# TriggerBoard_v4.net
KiCad netlist of a schematic drawn in EAGLE
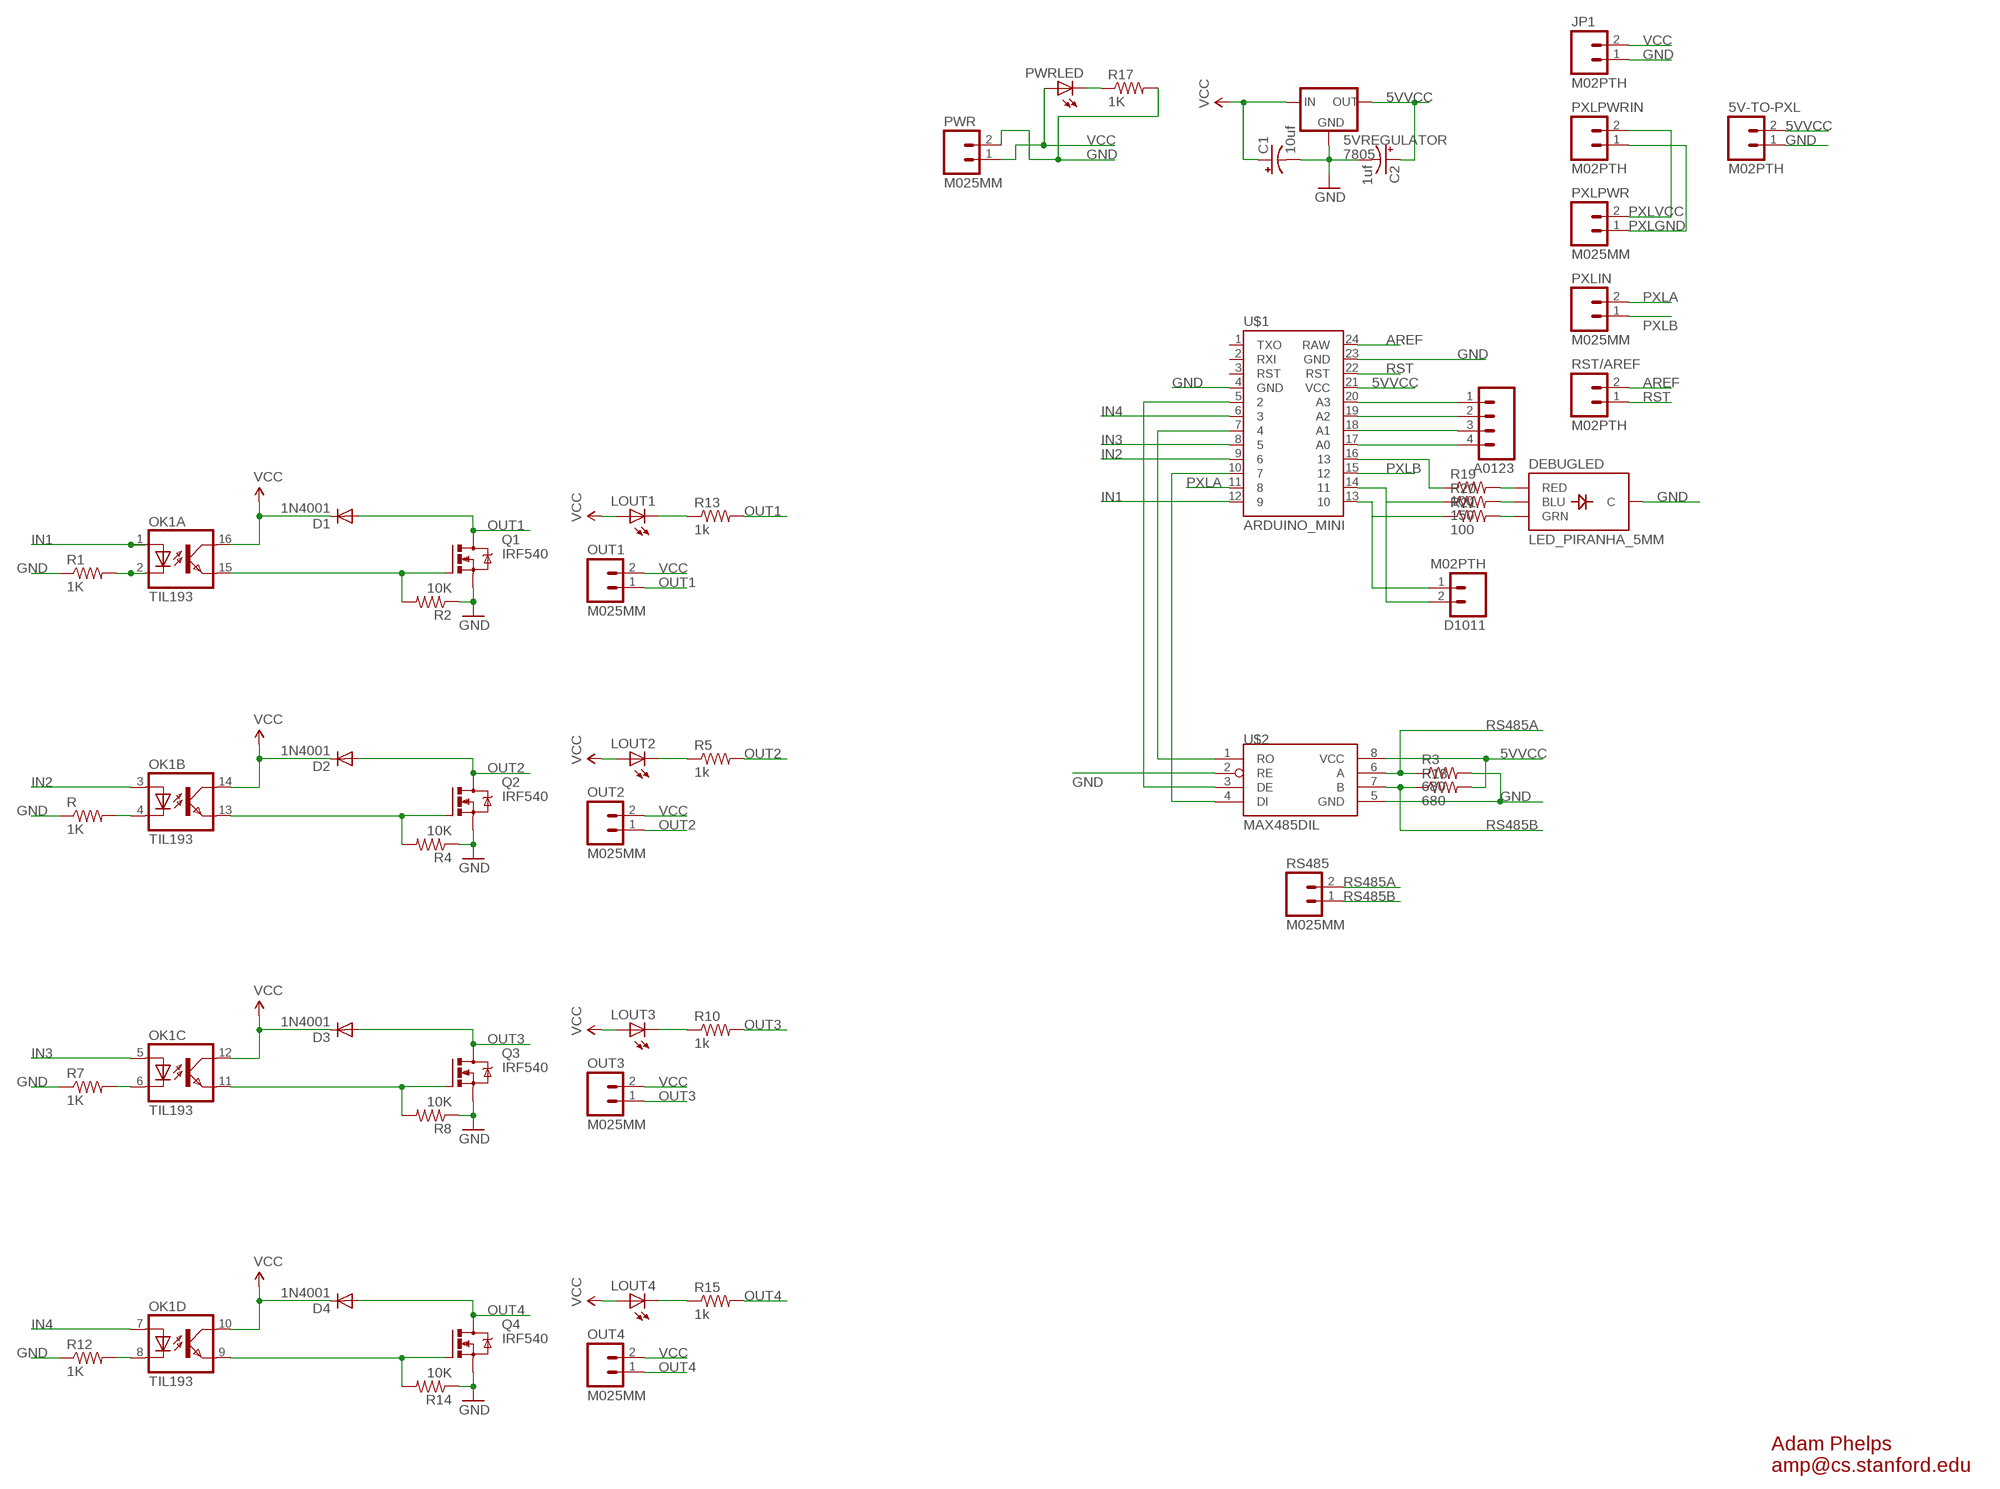
[diagram p0: schematic, sheet 1]

(export (version "E")
  (design (tool "Eeschema 10.0.6"))
  (components
    (comp (ref "5V-TO-PXL")
      (value "M02PTH")
      (footprint "eagle-import:1X02")
      (libsource (lib "eagle-import") (part "M02PTH"))
    )
    (comp (ref "5VREGULATOR")
      (value "7805")
      (footprint "eagle-import:TO220-IGO")
      (libsource (lib "eagle-import") (part "V_REG_78XXSINK"))
    )
    (comp (ref "A0123")
      (value "M04PTH")
      (footprint "eagle-import:1X04")
      (libsource (lib "eagle-import") (part "M04PTH"))
    )
    (comp (ref "C1")
      (value "10uf")
      (footprint "eagle-import:CPOL-RADIAL-10UF-25V")
      (libsource (lib "eagle-import") (part "CAP_POLPTH2"))
    )
    (comp (ref "C2")
      (value "1uf")
      (footprint "eagle-import:CPOL-RADIAL-10UF-25V")
      (libsource (lib "eagle-import") (part "CAP_POLPTH2"))
    )
    (comp (ref "D1")
      (value "1N4001")
      (footprint "eagle-import:DIODE-1N4001")
      (libsource (lib "eagle-import") (part "DIODEPTH"))
    )
    (comp (ref "D2")
      (value "1N4001")
      (footprint "eagle-import:DIODE-1N4001")
      (libsource (lib "eagle-import") (part "DIODEPTH"))
    )
    (comp (ref "D3")
      (value "1N4001")
      (footprint "eagle-import:DIODE-1N4001")
      (libsource (lib "eagle-import") (part "DIODEPTH"))
    )
    (comp (ref "D4")
      (value "1N4001")
      (footprint "eagle-import:DIODE-1N4001")
      (libsource (lib "eagle-import") (part "DIODEPTH"))
    )
    (comp (ref "D1011")
      (value "M02PTH")
      (footprint "eagle-import:1X02")
      (libsource (lib "eagle-import") (part "M02PTH"))
    )
    (comp (ref "DEBUGLED")
      (value "LED_PIRANHA_5MM")
      (footprint "eagle-import:LED_PIRANHA_5MM")
      (libsource (lib "eagle-import") (part "LED_PIRANHA_5MM"))
    )
    (comp (ref "JP1")
      (value "M02PTH")
      (footprint "eagle-import:1X02")
      (libsource (lib "eagle-import") (part "M02PTH"))
    )
    (comp (ref "LOUT1")
      (value "LED3MM")
      (footprint "eagle-import:LED3MM")
      (libsource (lib "eagle-import") (part "LED3MM"))
    )
    (comp (ref "LOUT2")
      (value "LED3MM")
      (footprint "eagle-import:LED3MM")
      (libsource (lib "eagle-import") (part "LED3MM"))
    )
    (comp (ref "LOUT3")
      (value "LED3MM")
      (footprint "eagle-import:LED3MM")
      (libsource (lib "eagle-import") (part "LED3MM"))
    )
    (comp (ref "LOUT4")
      (value "LED3MM")
      (footprint "eagle-import:LED3MM")
      (libsource (lib "eagle-import") (part "LED3MM"))
    )
    (comp (ref "OK1")
      (value "TIL193")
      (footprint "eagle-import:DIL16")
      (libsource (lib "eagle-import") (part "TIL193"))
    )
    (comp (ref "OUT1")
      (value "M025MM")
      (footprint "eagle-import:SCREWTERMINAL-5MM-2")
      (libsource (lib "eagle-import") (part "M025MM"))
    )
    (comp (ref "OUT2")
      (value "M025MM")
      (footprint "eagle-import:SCREWTERMINAL-5MM-2")
      (libsource (lib "eagle-import") (part "M025MM"))
    )
    (comp (ref "OUT3")
      (value "M025MM")
      (footprint "eagle-import:SCREWTERMINAL-5MM-2")
      (libsource (lib "eagle-import") (part "M025MM"))
    )
    (comp (ref "OUT4")
      (value "M025MM")
      (footprint "eagle-import:SCREWTERMINAL-5MM-2")
      (libsource (lib "eagle-import") (part "M025MM"))
    )
    (comp (ref "PWR")
      (value "M025MM")
      (footprint "eagle-import:SCREWTERMINAL-5MM-2")
      (libsource (lib "eagle-import") (part "M025MM"))
    )
    (comp (ref "PWRLED")
      (value "LED5MM")
      (footprint "eagle-import:LED5MM")
      (libsource (lib "eagle-import") (part "LED5MM"))
    )
    (comp (ref "PXLIN")
      (value "M025MM")
      (footprint "eagle-import:SCREWTERMINAL-5MM-2")
      (libsource (lib "eagle-import") (part "M025MM"))
    )
    (comp (ref "PXLPWR")
      (value "M025MM")
      (footprint "eagle-import:SCREWTERMINAL-5MM-2")
      (libsource (lib "eagle-import") (part "M025MM"))
    )
    (comp (ref "PXLPWRIN")
      (value "M02PTH")
      (footprint "eagle-import:1X02")
      (libsource (lib "eagle-import") (part "M02PTH"))
    )
    (comp (ref "Q1")
      (value "IRF540")
      (footprint "eagle-import:TO220BV")
      (libsource (lib "eagle-import") (part "IRF540"))
    )
    (comp (ref "Q2")
      (value "IRF540")
      (footprint "eagle-import:TO220BV")
      (libsource (lib "eagle-import") (part "IRF540"))
    )
    (comp (ref "Q3")
      (value "IRF540")
      (footprint "eagle-import:TO220BV")
      (libsource (lib "eagle-import") (part "IRF540"))
    )
    (comp (ref "Q4")
      (value "IRF540")
      (footprint "eagle-import:TO220BV")
      (libsource (lib "eagle-import") (part "IRF540"))
    )
    (comp (ref "R")
      (value "1K")
      (footprint "eagle-import:AXIAL-0.4")
      (libsource (lib "eagle-import") (part "RESISTORPTH-1/4W"))
    )
    (comp (ref "R1")
      (value "1K")
      (footprint "eagle-import:AXIAL-0.4")
      (libsource (lib "eagle-import") (part "RESISTORPTH-1/4W"))
    )
    (comp (ref "R2")
      (value "10K")
      (footprint "eagle-import:AXIAL-0.4")
      (libsource (lib "eagle-import") (part "RESISTORPTH-1/4W"))
    )
    (comp (ref "R3")
      (value "680")
      (footprint "eagle-import:AXIAL-0.4")
      (libsource (lib "eagle-import") (part "RESISTORPTH-1/4W"))
    )
    (comp (ref "R4")
      (value "10K")
      (footprint "eagle-import:AXIAL-0.4")
      (libsource (lib "eagle-import") (part "RESISTORPTH-1/4W"))
    )
    (comp (ref "R5")
      (value "1k")
      (footprint "eagle-import:AXIAL-0.4")
      (libsource (lib "eagle-import") (part "RESISTORPTH-1/4W"))
    )
    (comp (ref "R7")
      (value "1K")
      (footprint "eagle-import:AXIAL-0.4")
      (libsource (lib "eagle-import") (part "RESISTORPTH-1/4W"))
    )
    (comp (ref "R8")
      (value "10K")
      (footprint "eagle-import:AXIAL-0.4")
      (libsource (lib "eagle-import") (part "RESISTORPTH-1/4W"))
    )
    (comp (ref "R10")
      (value "1k")
      (footprint "eagle-import:AXIAL-0.4")
      (libsource (lib "eagle-import") (part "RESISTORPTH-1/4W"))
    )
    (comp (ref "R12")
      (value "1K")
      (footprint "eagle-import:AXIAL-0.4")
      (libsource (lib "eagle-import") (part "RESISTORPTH-1/4W"))
    )
    (comp (ref "R13")
      (value "1k")
      (footprint "eagle-import:AXIAL-0.4")
      (libsource (lib "eagle-import") (part "RESISTORPTH-1/4W"))
    )
    (comp (ref "R14")
      (value "10K")
      (footprint "eagle-import:AXIAL-0.4")
      (libsource (lib "eagle-import") (part "RESISTORPTH-1/4W"))
    )
    (comp (ref "R15")
      (value "1k")
      (footprint "eagle-import:AXIAL-0.4")
      (libsource (lib "eagle-import") (part "RESISTORPTH-1/4W"))
    )
    (comp (ref "R17")
      (value "1K")
      (footprint "eagle-import:AXIAL-0.4")
      (libsource (lib "eagle-import") (part "RESISTORPTH-1/4W"))
    )
    (comp (ref "R18")
      (value "680")
      (footprint "eagle-import:AXIAL-0.4")
      (libsource (lib "eagle-import") (part "RESISTORPTH-1/4W"))
    )
    (comp (ref "R19")
      (value "100")
      (footprint "eagle-import:AXIAL-0.4")
      (libsource (lib "eagle-import") (part "RESISTORPTH-1/4W"))
    )
    (comp (ref "R20")
      (value "150")
      (footprint "eagle-import:AXIAL-0.4")
      (libsource (lib "eagle-import") (part "RESISTORPTH-1/4W"))
    )
    (comp (ref "R21")
      (value "100")
      (footprint "eagle-import:AXIAL-0.4")
      (libsource (lib "eagle-import") (part "RESISTORPTH-1/4W"))
    )
    (comp (ref "RS485")
      (value "M025MM")
      (footprint "eagle-import:SCREWTERMINAL-5MM-2")
      (libsource (lib "eagle-import") (part "M025MM"))
    )
    (comp (ref "RST/AREF")
      (value "M02PTH")
      (footprint "eagle-import:1X02")
      (libsource (lib "eagle-import") (part "M02PTH"))
    )
    (comp (ref "U$1")
      (value "ARDUINO_MINI")
      (footprint "eagle-import:ARDUINO_MINI")
      (libsource (lib "eagle-import") (part "ARDUINO_MINI"))
    )
    (comp (ref "U$2")
      (value "MAX485DIL")
      (footprint "eagle-import:DIL08")
      (libsource (lib "eagle-import") (part "MAX485DIL"))
    )
  )
  (nets
    (net (code "1") (name "/5VVCC") (class "Default")
      (node (ref "5V-TO-PXL") (pin "2") (pinfunction "2_2") (pintype "passive"))
      (node (ref "5VREGULATOR") (pin "OUT") (pinfunction "OUT_OUT") (pintype "output"))
      (node (ref "C2") (pin "1") (pinfunction "+_1") (pintype "passive"))
      (node (ref "R18") (pin "P$2") (pinfunction "2_P$2") (pintype "passive"))
      (node (ref "U$1") (pin "21") (pinfunction "VCC_21") (pintype "bidirectional"))
      (node (ref "U$2") (pin "8") (pinfunction "VCC_8") (pintype "bidirectional"))
    )
    (net (code "2") (name "/AREF") (class "Default")
      (node (ref "RST/AREF") (pin "2") (pinfunction "2_2") (pintype "passive"))
      (node (ref "U$1") (pin "24") (pinfunction "RAW_24") (pintype "bidirectional"))
    )
    (net (code "3") (name "/IN1") (class "Default")
      (node (ref "OK1") (pin "1") (pinfunction "A_1") (pintype "passive"))
      (node (ref "U$1") (pin "12") (pinfunction "9_12") (pintype "bidirectional"))
    )
    (net (code "4") (name "/IN2") (class "Default")
      (node (ref "OK1") (pin "3") (pinfunction "A_3") (pintype "passive"))
      (node (ref "U$1") (pin "9") (pinfunction "6_9") (pintype "bidirectional"))
    )
    (net (code "5") (name "/IN3") (class "Default")
      (node (ref "OK1") (pin "5") (pinfunction "A_5") (pintype "passive"))
      (node (ref "U$1") (pin "8") (pinfunction "5_8") (pintype "bidirectional"))
    )
    (net (code "6") (name "/IN4") (class "Default")
      (node (ref "OK1") (pin "7") (pinfunction "A_7") (pintype "passive"))
      (node (ref "U$1") (pin "6") (pinfunction "3_6") (pintype "bidirectional"))
    )
    (net (code "7") (name "/OUT1") (class "Default")
      (node (ref "D1") (pin "A") (pinfunction "A_A") (pintype "passive"))
      (node (ref "OUT1") (pin "1") (pinfunction "1_1") (pintype "passive"))
      (node (ref "Q1") (pin "D") (pinfunction "D_D") (pintype "passive"))
      (node (ref "R13") (pin "P$2") (pinfunction "2_P$2") (pintype "passive"))
    )
    (net (code "8") (name "/OUT2") (class "Default")
      (node (ref "D2") (pin "A") (pinfunction "A_A") (pintype "passive"))
      (node (ref "OUT2") (pin "1") (pinfunction "1_1") (pintype "passive"))
      (node (ref "Q2") (pin "D") (pinfunction "D_D") (pintype "passive"))
      (node (ref "R5") (pin "P$2") (pinfunction "2_P$2") (pintype "passive"))
    )
    (net (code "9") (name "/OUT3") (class "Default")
      (node (ref "D3") (pin "A") (pinfunction "A_A") (pintype "passive"))
      (node (ref "OUT3") (pin "1") (pinfunction "1_1") (pintype "passive"))
      (node (ref "Q3") (pin "D") (pinfunction "D_D") (pintype "passive"))
      (node (ref "R10") (pin "P$2") (pinfunction "2_P$2") (pintype "passive"))
    )
    (net (code "10") (name "/OUT4") (class "Default")
      (node (ref "D4") (pin "A") (pinfunction "A_A") (pintype "passive"))
      (node (ref "OUT4") (pin "1") (pinfunction "1_1") (pintype "passive"))
      (node (ref "Q4") (pin "D") (pinfunction "D_D") (pintype "passive"))
      (node (ref "R15") (pin "P$2") (pinfunction "2_P$2") (pintype "passive"))
    )
    (net (code "11") (name "/PXLA") (class "Default")
      (node (ref "PXLIN") (pin "2") (pinfunction "2_2") (pintype "passive"))
      (node (ref "U$1") (pin "11") (pinfunction "8_11") (pintype "bidirectional"))
    )
    (net (code "12") (name "/PXLB") (class "Default")
      (node (ref "PXLIN") (pin "1") (pinfunction "1_1") (pintype "passive"))
      (node (ref "U$1") (pin "15") (pinfunction "12_15") (pintype "bidirectional"))
    )
    (net (code "13") (name "/PXLGND") (class "Default")
      (node (ref "PXLPWR") (pin "1") (pinfunction "1_1") (pintype "passive"))
      (node (ref "PXLPWRIN") (pin "1") (pinfunction "1_1") (pintype "passive"))
    )
    (net (code "14") (name "/PXLVCC") (class "Default")
      (node (ref "PXLPWR") (pin "2") (pinfunction "2_2") (pintype "passive"))
      (node (ref "PXLPWRIN") (pin "2") (pinfunction "2_2") (pintype "passive"))
    )
    (net (code "15") (name "/RS485A") (class "Default")
      (node (ref "R3") (pin "P$1") (pinfunction "1_P$1") (pintype "passive"))
      (node (ref "RS485") (pin "2") (pinfunction "2_2") (pintype "passive"))
      (node (ref "U$2") (pin "6") (pinfunction "A_6") (pintype "bidirectional"))
    )
    (net (code "16") (name "/RS485B") (class "Default")
      (node (ref "R18") (pin "P$1") (pinfunction "1_P$1") (pintype "passive"))
      (node (ref "RS485") (pin "1") (pinfunction "1_1") (pintype "passive"))
      (node (ref "U$2") (pin "7") (pinfunction "B_7") (pintype "bidirectional"))
    )
    (net (code "17") (name "/RST") (class "Default")
      (node (ref "RST/AREF") (pin "1") (pinfunction "1_1") (pintype "passive"))
      (node (ref "U$1") (pin "22") (pinfunction "RST_22") (pintype "bidirectional"))
    )
    (net (code "18") (name "GND") (class "Default")
      (node (ref "5V-TO-PXL") (pin "1") (pinfunction "1_1") (pintype "passive"))
      (node (ref "5VREGULATOR") (pin "GND") (pinfunction "GND_GND") (pintype "input"))
      (node (ref "C1") (pin "2") (pinfunction "-_2") (pintype "passive"))
      (node (ref "C2") (pin "2") (pinfunction "-_2") (pintype "passive"))
      (node (ref "DEBUGLED") (pin "-") (pinfunction "C_-") (pintype "bidirectional"))
      (node (ref "JP1") (pin "1") (pinfunction "1_1") (pintype "passive"))
      (node (ref "PWR") (pin "2") (pinfunction "2_2") (pintype "passive"))
      (node (ref "Q1") (pin "S") (pinfunction "S_S") (pintype "passive"))
      (node (ref "Q2") (pin "S") (pinfunction "S_S") (pintype "passive"))
      (node (ref "Q3") (pin "S") (pinfunction "S_S") (pintype "passive"))
      (node (ref "Q4") (pin "S") (pinfunction "S_S") (pintype "passive"))
      (node (ref "R") (pin "P$1") (pinfunction "1_P$1") (pintype "passive"))
      (node (ref "R1") (pin "P$1") (pinfunction "1_P$1") (pintype "passive"))
      (node (ref "R12") (pin "P$1") (pinfunction "1_P$1") (pintype "passive"))
      (node (ref "R14") (pin "P$1") (pinfunction "1_P$1") (pintype "passive"))
      (node (ref "R17") (pin "P$2") (pinfunction "2_P$2") (pintype "passive"))
      (node (ref "R2") (pin "P$1") (pinfunction "1_P$1") (pintype "passive"))
      (node (ref "R3") (pin "P$2") (pinfunction "2_P$2") (pintype "passive"))
      (node (ref "R4") (pin "P$1") (pinfunction "1_P$1") (pintype "passive"))
      (node (ref "R7") (pin "P$1") (pinfunction "1_P$1") (pintype "passive"))
      (node (ref "R8") (pin "P$1") (pinfunction "1_P$1") (pintype "passive"))
      (node (ref "U$1") (pin "23") (pinfunction "GND_23") (pintype "bidirectional"))
      (node (ref "U$1") (pin "4") (pinfunction "GND_4") (pintype "bidirectional"))
      (node (ref "U$2") (pin "2") (pinfunction "RE_2") (pintype "bidirectional"))
      (node (ref "U$2") (pin "5") (pinfunction "GND_5") (pintype "bidirectional"))
    )
    (net (code "19") (name "Net-(DEBUGLED-BLU)") (class "Default")
      (node (ref "DEBUGLED") (pin "B") (pinfunction "BLU_B") (pintype "bidirectional"))
      (node (ref "R20") (pin "P$2") (pinfunction "2_P$2") (pintype "passive"))
    )
    (net (code "20") (name "Net-(DEBUGLED-GRN)") (class "Default")
      (node (ref "DEBUGLED") (pin "G") (pinfunction "GRN_G") (pintype "bidirectional"))
      (node (ref "R21") (pin "P$2") (pinfunction "2_P$2") (pintype "passive"))
    )
    (net (code "21") (name "Net-(DEBUGLED-RED)") (class "Default")
      (node (ref "DEBUGLED") (pin "R") (pinfunction "RED_R") (pintype "bidirectional"))
      (node (ref "R19") (pin "P$2") (pinfunction "2_P$2") (pintype "passive"))
    )
    (net (code "22") (name "Net-(LOUT1-C)") (class "Default")
      (node (ref "LOUT1") (pin "K") (pinfunction "C_K") (pintype "passive"))
      (node (ref "R13") (pin "P$1") (pinfunction "1_P$1") (pintype "passive"))
    )
    (net (code "23") (name "Net-(LOUT2-C)") (class "Default")
      (node (ref "LOUT2") (pin "K") (pinfunction "C_K") (pintype "passive"))
      (node (ref "R5") (pin "P$1") (pinfunction "1_P$1") (pintype "passive"))
    )
    (net (code "24") (name "Net-(LOUT3-C)") (class "Default")
      (node (ref "LOUT3") (pin "K") (pinfunction "C_K") (pintype "passive"))
      (node (ref "R10") (pin "P$1") (pinfunction "1_P$1") (pintype "passive"))
    )
    (net (code "25") (name "Net-(LOUT4-C)") (class "Default")
      (node (ref "LOUT4") (pin "K") (pinfunction "C_K") (pintype "passive"))
      (node (ref "R15") (pin "P$1") (pinfunction "1_P$1") (pintype "passive"))
    )
    (net (code "26") (name "Net-(OK1A-C)") (class "Default")
      (node (ref "OK1") (pin "2") (pinfunction "C_2") (pintype "passive"))
      (node (ref "R1") (pin "P$2") (pinfunction "2_P$2") (pintype "passive"))
    )
    (net (code "27") (name "Net-(OK1A-EMIT)") (class "Default")
      (node (ref "OK1") (pin "15") (pinfunction "EMIT_15") (pintype "passive"))
      (node (ref "Q1") (pin "G") (pinfunction "G_G") (pintype "passive"))
      (node (ref "R2") (pin "P$2") (pinfunction "2_P$2") (pintype "passive"))
    )
    (net (code "28") (name "Net-(OK1B-C)") (class "Default")
      (node (ref "OK1") (pin "4") (pinfunction "C_4") (pintype "passive"))
      (node (ref "R") (pin "P$2") (pinfunction "2_P$2") (pintype "passive"))
    )
    (net (code "29") (name "Net-(OK1B-EMIT)") (class "Default")
      (node (ref "OK1") (pin "13") (pinfunction "EMIT_13") (pintype "passive"))
      (node (ref "Q2") (pin "G") (pinfunction "G_G") (pintype "passive"))
      (node (ref "R4") (pin "P$2") (pinfunction "2_P$2") (pintype "passive"))
    )
    (net (code "30") (name "Net-(OK1C-C)") (class "Default")
      (node (ref "OK1") (pin "6") (pinfunction "C_6") (pintype "passive"))
      (node (ref "R7") (pin "P$2") (pinfunction "2_P$2") (pintype "passive"))
    )
    (net (code "31") (name "Net-(OK1C-EMIT)") (class "Default")
      (node (ref "OK1") (pin "11") (pinfunction "EMIT_11") (pintype "passive"))
      (node (ref "Q3") (pin "G") (pinfunction "G_G") (pintype "passive"))
      (node (ref "R8") (pin "P$2") (pinfunction "2_P$2") (pintype "passive"))
    )
    (net (code "32") (name "Net-(OK1D-C)") (class "Default")
      (node (ref "OK1") (pin "8") (pinfunction "C_8") (pintype "passive"))
      (node (ref "R12") (pin "P$2") (pinfunction "2_P$2") (pintype "passive"))
    )
    (net (code "33") (name "Net-(OK1D-EMIT)") (class "Default")
      (node (ref "OK1") (pin "9") (pinfunction "EMIT_9") (pintype "passive"))
      (node (ref "Q4") (pin "G") (pinfunction "G_G") (pintype "passive"))
      (node (ref "R14") (pin "P$2") (pinfunction "2_P$2") (pintype "passive"))
    )
    (net (code "34") (name "Net-(PWRLED-C)") (class "Default")
      (node (ref "PWRLED") (pin "K") (pinfunction "C_K") (pintype "passive"))
      (node (ref "R17") (pin "P$1") (pinfunction "1_P$1") (pintype "passive"))
    )
    (net (code "35") (name "Net-(R19-1)") (class "Default")
      (node (ref "R19") (pin "P$1") (pinfunction "1_P$1") (pintype "passive"))
      (node (ref "U$1") (pin "16") (pinfunction "13_16") (pintype "bidirectional"))
    )
    (net (code "36") (name "Net-(R20-1)") (class "Default")
      (node (ref "D1011") (pin "2") (pinfunction "2_2") (pintype "passive"))
      (node (ref "R20") (pin "P$1") (pinfunction "1_P$1") (pintype "passive"))
      (node (ref "U$1") (pin "14") (pinfunction "11_14") (pintype "bidirectional"))
    )
    (net (code "37") (name "Net-(R21-1)") (class "Default")
      (node (ref "D1011") (pin "1") (pinfunction "1_1") (pintype "passive"))
      (node (ref "R21") (pin "P$1") (pinfunction "1_P$1") (pintype "passive"))
      (node (ref "U$1") (pin "13") (pinfunction "10_13") (pintype "bidirectional"))
    )
    (net (code "38") (name "Net-(U$1-2)") (class "Default")
      (node (ref "U$1") (pin "5") (pinfunction "2_5") (pintype "bidirectional"))
      (node (ref "U$2") (pin "3") (pinfunction "DE_3") (pintype "bidirectional"))
    )
    (net (code "39") (name "Net-(U$1-4)") (class "Default")
      (node (ref "U$1") (pin "7") (pinfunction "4_7") (pintype "bidirectional"))
      (node (ref "U$2") (pin "1") (pinfunction "RO_1") (pintype "bidirectional"))
    )
    (net (code "40") (name "Net-(U$1-7)") (class "Default")
      (node (ref "U$1") (pin "10") (pinfunction "7_10") (pintype "bidirectional"))
      (node (ref "U$2") (pin "4") (pinfunction "DI_4") (pintype "bidirectional"))
    )
    (net (code "41") (name "Net-(U$1-A0)") (class "Default")
      (node (ref "A0123") (pin "4") (pinfunction "4_4") (pintype "passive"))
      (node (ref "U$1") (pin "17") (pinfunction "A0_17") (pintype "bidirectional"))
    )
    (net (code "42") (name "Net-(U$1-A1)") (class "Default")
      (node (ref "A0123") (pin "3") (pinfunction "3_3") (pintype "passive"))
      (node (ref "U$1") (pin "18") (pinfunction "A1_18") (pintype "bidirectional"))
    )
    (net (code "43") (name "Net-(U$1-A2)") (class "Default")
      (node (ref "A0123") (pin "2") (pinfunction "2_2") (pintype "passive"))
      (node (ref "U$1") (pin "19") (pinfunction "A2_19") (pintype "bidirectional"))
    )
    (net (code "44") (name "Net-(U$1-A3)") (class "Default")
      (node (ref "A0123") (pin "1") (pinfunction "1_1") (pintype "passive"))
      (node (ref "U$1") (pin "20") (pinfunction "A3_20") (pintype "bidirectional"))
    )
    (net (code "45") (name "VCC") (class "Default")
      (node (ref "5VREGULATOR") (pin "IN") (pinfunction "IN_IN") (pintype "input"))
      (node (ref "C1") (pin "1") (pinfunction "+_1") (pintype "passive"))
      (node (ref "D1") (pin "C") (pinfunction "C_C") (pintype "passive"))
      (node (ref "D2") (pin "C") (pinfunction "C_C") (pintype "passive"))
      (node (ref "D3") (pin "C") (pinfunction "C_C") (pintype "passive"))
      (node (ref "D4") (pin "C") (pinfunction "C_C") (pintype "passive"))
      (node (ref "JP1") (pin "2") (pinfunction "2_2") (pintype "passive"))
      (node (ref "LOUT1") (pin "A") (pinfunction "A_A") (pintype "passive"))
      (node (ref "LOUT2") (pin "A") (pinfunction "A_A") (pintype "passive"))
      (node (ref "LOUT3") (pin "A") (pinfunction "A_A") (pintype "passive"))
      (node (ref "LOUT4") (pin "A") (pinfunction "A_A") (pintype "passive"))
      (node (ref "OK1") (pin "10") (pinfunction "COL_10") (pintype "passive"))
      (node (ref "OK1") (pin "12") (pinfunction "COL_12") (pintype "passive"))
      (node (ref "OK1") (pin "14") (pinfunction "COL_14") (pintype "passive"))
      (node (ref "OK1") (pin "16") (pinfunction "COL_16") (pintype "passive"))
      (node (ref "OUT1") (pin "2") (pinfunction "2_2") (pintype "passive"))
      (node (ref "OUT2") (pin "2") (pinfunction "2_2") (pintype "passive"))
      (node (ref "OUT3") (pin "2") (pinfunction "2_2") (pintype "passive"))
      (node (ref "OUT4") (pin "2") (pinfunction "2_2") (pintype "passive"))
      (node (ref "PWR") (pin "1") (pinfunction "1_1") (pintype "passive"))
      (node (ref "PWRLED") (pin "A") (pinfunction "A_A") (pintype "passive"))
    )
    (net (code "46") (name "unconnected-(U$1-RST-Pad3)") (class "Default")
      (node (ref "U$1") (pin "3") (pinfunction "RST_3") (pintype "bidirectional"))
    )
    (net (code "47") (name "unconnected-(U$1-RXI-Pad2)") (class "Default")
      (node (ref "U$1") (pin "2") (pinfunction "RXI_2") (pintype "bidirectional"))
    )
    (net (code "48") (name "unconnected-(U$1-TXO-Pad1)") (class "Default")
      (node (ref "U$1") (pin "1") (pinfunction "TXO_1") (pintype "bidirectional"))
    )
  )
)
